# SCH_sfstgr_2023-11-16.net
KiCad netlist of a schematic drawn in EasyEDA
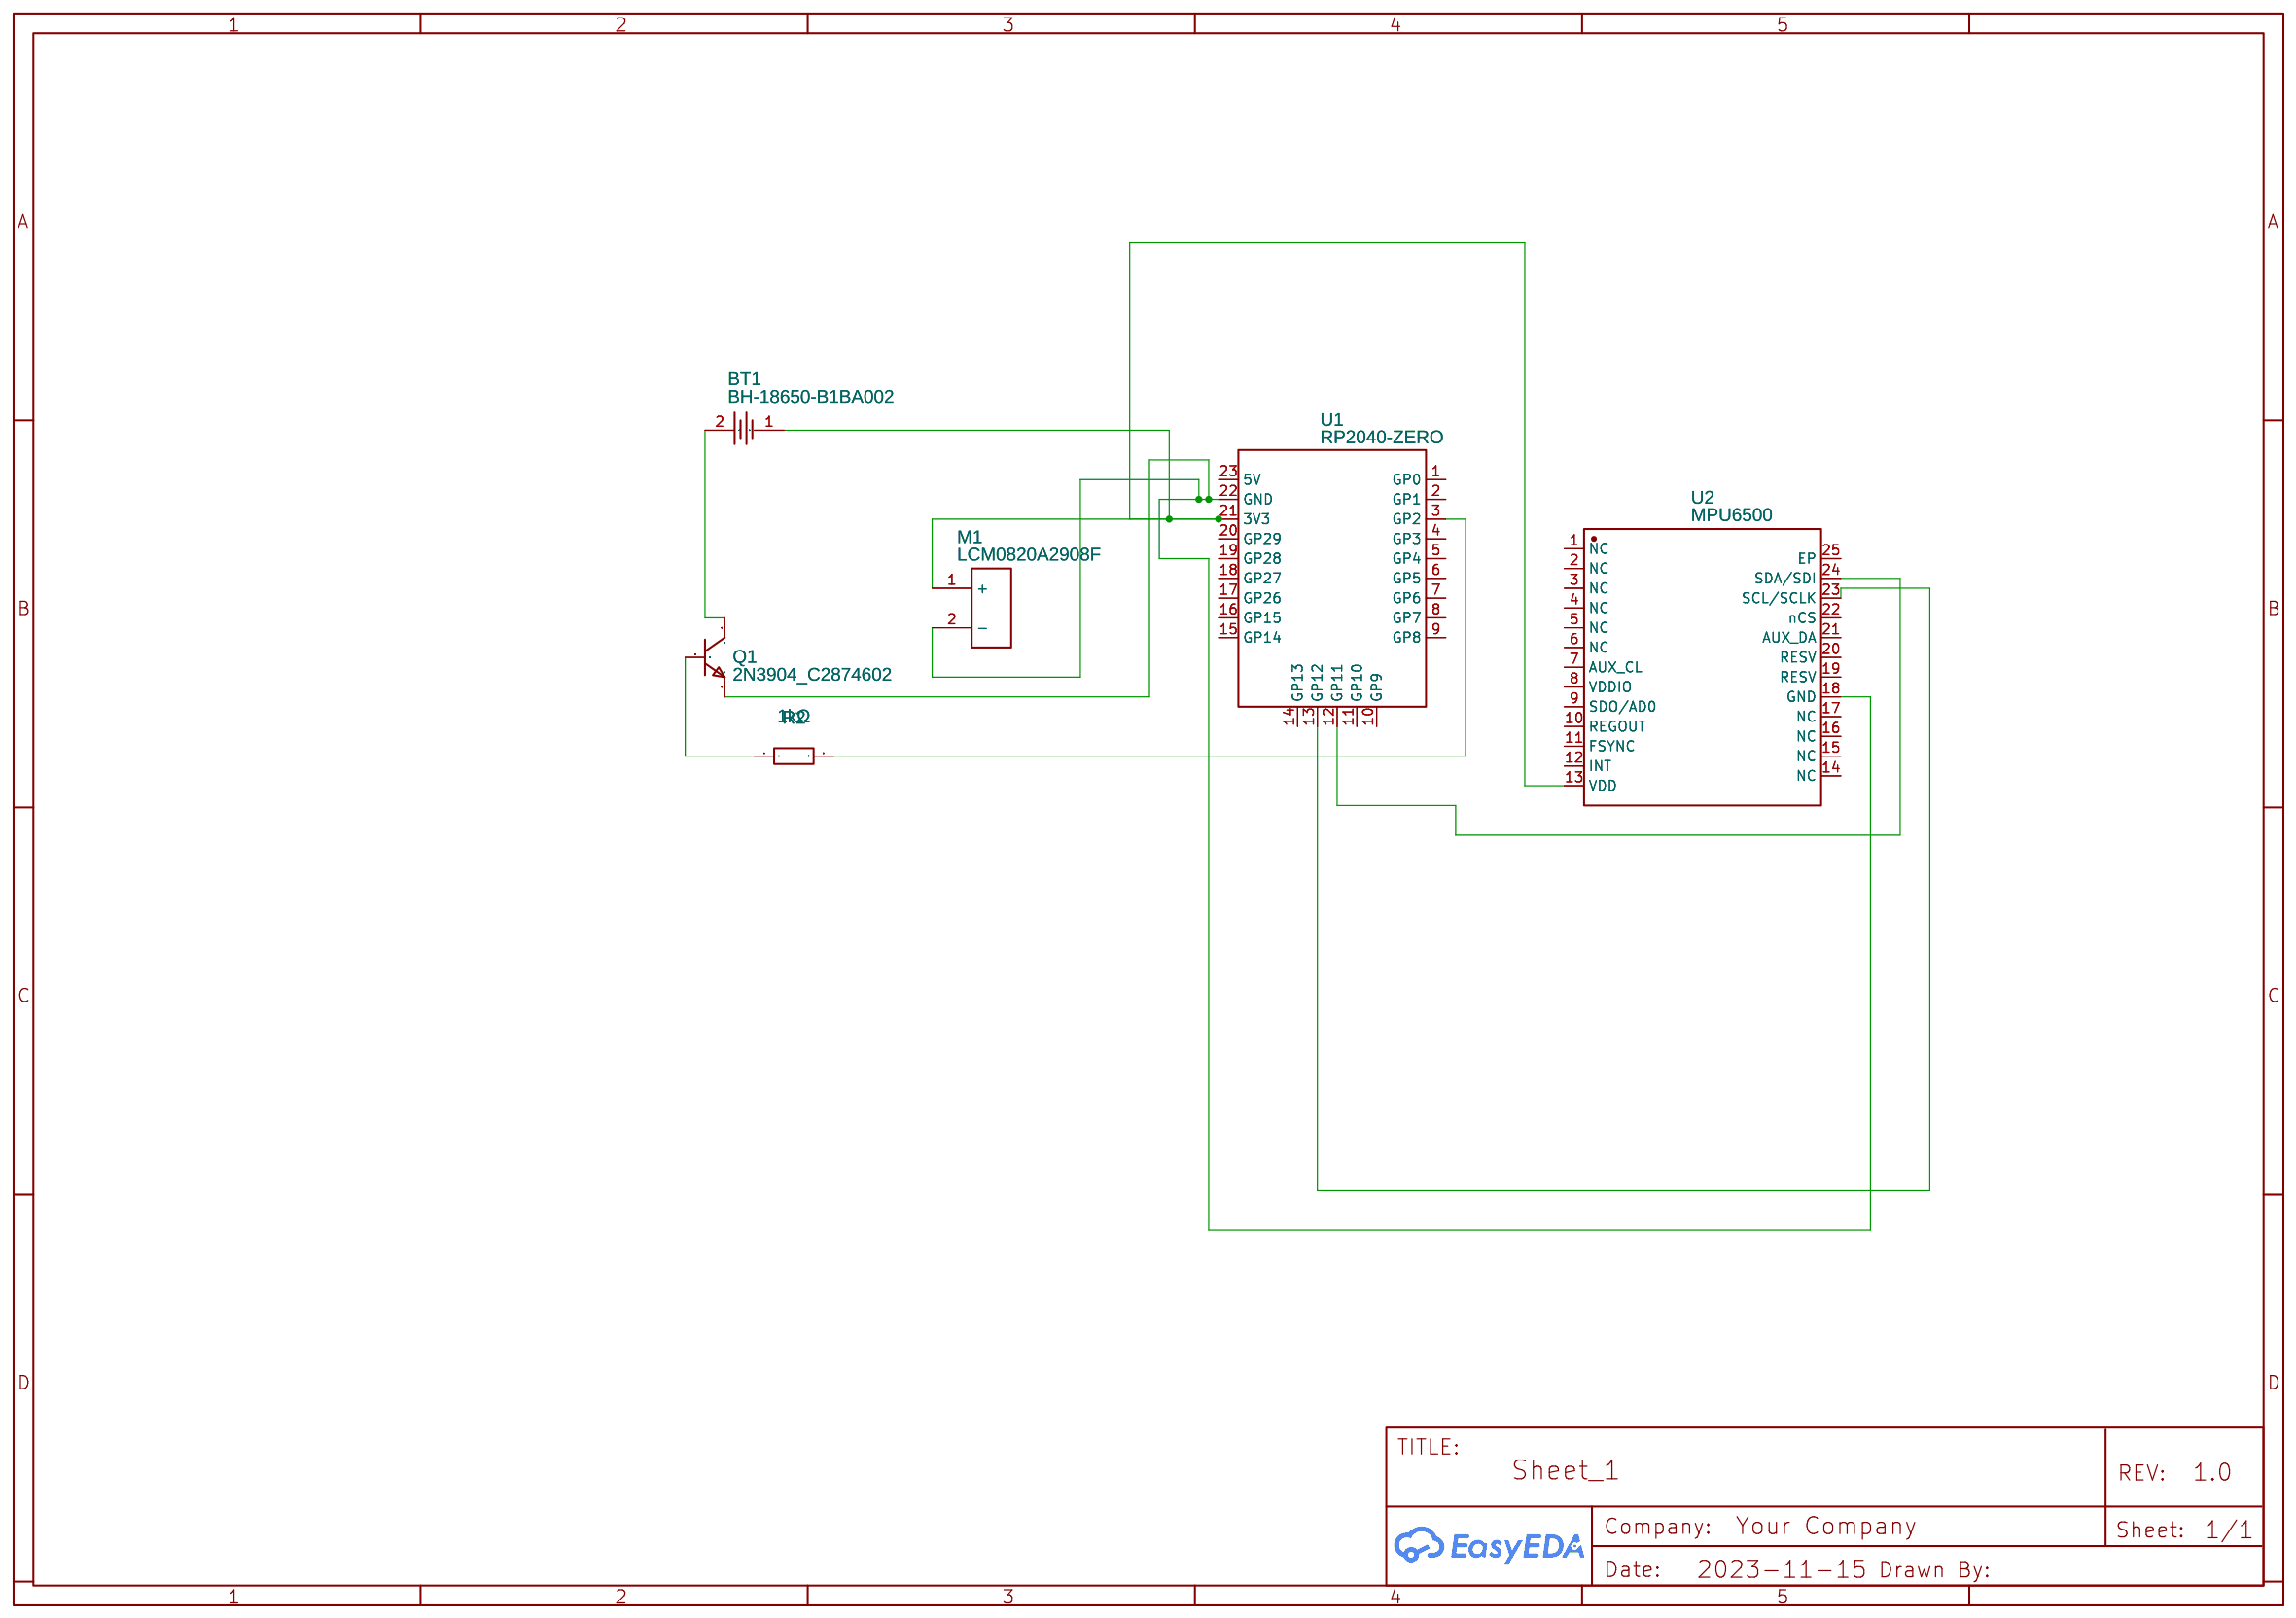
[diagram p0: schematic sheet]

(export (version "E")
  (design (tool "Eeschema 10.0.6"))
  (components
    (comp (ref "BT1")
      (value "BH-18650-B1BA002")
      (fields (field (name "Manufacturer") "MYOUNG(美阳)"))
      (libsource (lib "") (part "BH-18650-B1BA002"))
    )
    (comp (ref "M1") (value "LCM0820A2908F") (libsource (lib "") (part "LCM0820A2908F")))
    (comp (ref "Q1")
      (value "2N3904_C2874602")
      (fields (field (name "Manufacturer Part") "2N3904") (field (name "Manufacturer") "JSMSEMI(杰盛微)"))
      (libsource (lib "") (part "2N3904_C2874602"))
    )
    (comp (ref "R2")
      (value "1kΩ")
      (fields
        (field (name "Manufacturer Part") "QR0402F1K00Q10Z")
        (field (name "Manufacturer") "EVER OHMS(天二科技)")
      )
      (libsource (lib "") (part "QR0402F1KQ10"))
    )
    (comp (ref "U1")
      (value "RP2040-ZERO")
      (fields
        (field (name "Manufacturer Part") "RP2040-Zero")
        (field (name "Manufacturer") "Waveshare(微雪电子)")
      )
      (libsource (lib "") (part "RP2040-ZERO"))
    )
    (comp (ref "U2")
      (value "MPU6500")
      (fields (field (name "Manufacturer") "TDK InvenSense(应美盛)"))
      (libsource (lib "") (part "MPU6500"))
    )
  )
  (nets
    (net (code "1") (name "Net-(M1-+)") (class "Default")
      (node (ref "BT1") (pin "1") (pinfunction "1_1") (pintype "input"))
      (node (ref "M1") (pin "1") (pinfunction "+_1") (pintype "unspecified"))
      (node (ref "U1") (pin "21") (pinfunction "3V3_21") (pintype "unspecified"))
      (node (ref "U2") (pin "13") (pinfunction "VDD_13") (pintype "unspecified"))
    )
    (net (code "2") (name "Net-(M1--)") (class "Default")
      (node (ref "M1") (pin "2") (pinfunction "-_2") (pintype "unspecified"))
      (node (ref "Q1") (pin "1") (pinfunction "E_1") (pintype "unspecified"))
      (node (ref "U1") (pin "22") (pinfunction "GND_22") (pintype "unspecified"))
      (node (ref "U2") (pin "18") (pinfunction "GND_18") (pintype "unspecified"))
    )
    (net (code "3") (name "Net-(Q1-B)") (class "Default")
      (node (ref "Q1") (pin "2") (pinfunction "B_2") (pintype "unspecified"))
      (node (ref "R2") (pin "1") (pinfunction "1_1") (pintype "unspecified"))
    )
    (net (code "4") (name "Net-(Q1-C)") (class "Default")
      (node (ref "BT1") (pin "2") (pinfunction "2_2") (pintype "input"))
      (node (ref "Q1") (pin "3") (pinfunction "C_3") (pintype "unspecified"))
    )
    (net (code "5") (name "Net-(U1-GP2)") (class "Default")
      (node (ref "R2") (pin "2") (pinfunction "2_2") (pintype "unspecified"))
      (node (ref "U1") (pin "3") (pinfunction "GP2_3") (pintype "unspecified"))
    )
    (net (code "6") (name "Net-(U1-GP11)") (class "Default")
      (node (ref "U1") (pin "12") (pinfunction "GP11_12") (pintype "unspecified"))
      (node (ref "U2") (pin "24") (pinfunction "SDA/SDI_24") (pintype "unspecified"))
    )
    (net (code "7") (name "Net-(U1-GP12)") (class "Default")
      (node (ref "U1") (pin "13") (pinfunction "GP12_13") (pintype "unspecified"))
      (node (ref "U2") (pin "23") (pinfunction "SCL/SCLK_23") (pintype "unspecified"))
    )
    (net (code "8") (name "unconnected-(U1-5V-Pad23)") (class "Default")
      (node (ref "U1") (pin "23") (pinfunction "5V_23") (pintype "unspecified"))
    )
    (net (code "9") (name "unconnected-(U1-GP0-Pad1)") (class "Default")
      (node (ref "U1") (pin "1") (pinfunction "GP0_1") (pintype "unspecified"))
    )
    (net (code "10") (name "unconnected-(U1-GP1-Pad2)") (class "Default")
      (node (ref "U1") (pin "2") (pinfunction "GP1_2") (pintype "unspecified"))
    )
    (net (code "11") (name "unconnected-(U1-GP3-Pad4)") (class "Default")
      (node (ref "U1") (pin "4") (pinfunction "GP3_4") (pintype "unspecified"))
    )
    (net (code "12") (name "unconnected-(U1-GP4-Pad5)") (class "Default")
      (node (ref "U1") (pin "5") (pinfunction "GP4_5") (pintype "unspecified"))
    )
    (net (code "13") (name "unconnected-(U1-GP5-Pad6)") (class "Default")
      (node (ref "U1") (pin "6") (pinfunction "GP5_6") (pintype "unspecified"))
    )
    (net (code "14") (name "unconnected-(U1-GP6-Pad7)") (class "Default")
      (node (ref "U1") (pin "7") (pinfunction "GP6_7") (pintype "unspecified"))
    )
    (net (code "15") (name "unconnected-(U1-GP7-Pad8)") (class "Default")
      (node (ref "U1") (pin "8") (pinfunction "GP7_8") (pintype "unspecified"))
    )
    (net (code "16") (name "unconnected-(U1-GP8-Pad9)") (class "Default")
      (node (ref "U1") (pin "9") (pinfunction "GP8_9") (pintype "unspecified"))
    )
    (net (code "17") (name "unconnected-(U1-GP9-Pad10)") (class "Default")
      (node (ref "U1") (pin "10") (pinfunction "GP9_10") (pintype "unspecified"))
    )
    (net (code "18") (name "unconnected-(U1-GP10-Pad11)") (class "Default")
      (node (ref "U1") (pin "11") (pinfunction "GP10_11") (pintype "unspecified"))
    )
    (net (code "19") (name "unconnected-(U1-GP13-Pad14)") (class "Default")
      (node (ref "U1") (pin "14") (pinfunction "GP13_14") (pintype "unspecified"))
    )
    (net (code "20") (name "unconnected-(U1-GP14-Pad15)") (class "Default")
      (node (ref "U1") (pin "15") (pinfunction "GP14_15") (pintype "unspecified"))
    )
    (net (code "21") (name "unconnected-(U1-GP15-Pad16)") (class "Default")
      (node (ref "U1") (pin "16") (pinfunction "GP15_16") (pintype "unspecified"))
    )
    (net (code "22") (name "unconnected-(U1-GP26-Pad17)") (class "Default")
      (node (ref "U1") (pin "17") (pinfunction "GP26_17") (pintype "unspecified"))
    )
    (net (code "23") (name "unconnected-(U1-GP27-Pad18)") (class "Default")
      (node (ref "U1") (pin "18") (pinfunction "GP27_18") (pintype "unspecified"))
    )
    (net (code "24") (name "unconnected-(U1-GP28-Pad19)") (class "Default")
      (node (ref "U1") (pin "19") (pinfunction "GP28_19") (pintype "unspecified"))
    )
    (net (code "25") (name "unconnected-(U1-GP29-Pad20)") (class "Default")
      (node (ref "U1") (pin "20") (pinfunction "GP29_20") (pintype "unspecified"))
    )
    (net (code "26") (name "unconnected-(U2-AUX_CL-Pad7)") (class "Default")
      (node (ref "U2") (pin "7") (pinfunction "AUX_CL_7") (pintype "unspecified"))
    )
    (net (code "27") (name "unconnected-(U2-AUX_DA-Pad21)") (class "Default")
      (node (ref "U2") (pin "21") (pinfunction "AUX_DA_21") (pintype "unspecified"))
    )
    (net (code "28") (name "unconnected-(U2-EP-Pad25)") (class "Default")
      (node (ref "U2") (pin "25") (pinfunction "EP_25") (pintype "unspecified"))
    )
    (net (code "29") (name "unconnected-(U2-FSYNC-Pad11)") (class "Default")
      (node (ref "U2") (pin "11") (pinfunction "FSYNC_11") (pintype "unspecified"))
    )
    (net (code "30") (name "unconnected-(U2-INT-Pad12)") (class "Default")
      (node (ref "U2") (pin "12") (pinfunction "INT_12") (pintype "unspecified"))
    )
    (net (code "31") (name "unconnected-(U2-NC-Pad1)") (class "Default")
      (node (ref "U2") (pin "1") (pinfunction "NC_1") (pintype "unspecified"))
    )
    (net (code "32") (name "unconnected-(U2-NC-Pad2)") (class "Default")
      (node (ref "U2") (pin "2") (pinfunction "NC_2") (pintype "unspecified"))
    )
    (net (code "33") (name "unconnected-(U2-NC-Pad3)") (class "Default")
      (node (ref "U2") (pin "3") (pinfunction "NC_3") (pintype "unspecified"))
    )
    (net (code "34") (name "unconnected-(U2-NC-Pad4)") (class "Default")
      (node (ref "U2") (pin "4") (pinfunction "NC_4") (pintype "unspecified"))
    )
    (net (code "35") (name "unconnected-(U2-NC-Pad5)") (class "Default")
      (node (ref "U2") (pin "5") (pinfunction "NC_5") (pintype "unspecified"))
    )
    (net (code "36") (name "unconnected-(U2-NC-Pad6)") (class "Default")
      (node (ref "U2") (pin "6") (pinfunction "NC_6") (pintype "unspecified"))
    )
    (net (code "37") (name "unconnected-(U2-NC-Pad14)") (class "Default")
      (node (ref "U2") (pin "14") (pinfunction "NC_14") (pintype "unspecified"))
    )
    (net (code "38") (name "unconnected-(U2-NC-Pad15)") (class "Default")
      (node (ref "U2") (pin "15") (pinfunction "NC_15") (pintype "unspecified"))
    )
    (net (code "39") (name "unconnected-(U2-NC-Pad16)") (class "Default")
      (node (ref "U2") (pin "16") (pinfunction "NC_16") (pintype "unspecified"))
    )
    (net (code "40") (name "unconnected-(U2-NC-Pad17)") (class "Default")
      (node (ref "U2") (pin "17") (pinfunction "NC_17") (pintype "unspecified"))
    )
    (net (code "41") (name "unconnected-(U2-REGOUT-Pad10)") (class "Default")
      (node (ref "U2") (pin "10") (pinfunction "REGOUT_10") (pintype "unspecified"))
    )
    (net (code "42") (name "unconnected-(U2-RESV-Pad19)") (class "Default")
      (node (ref "U2") (pin "19") (pinfunction "RESV_19") (pintype "unspecified"))
    )
    (net (code "43") (name "unconnected-(U2-RESV-Pad20)") (class "Default")
      (node (ref "U2") (pin "20") (pinfunction "RESV_20") (pintype "unspecified"))
    )
    (net (code "44") (name "unconnected-(U2-SDO{slash}AD0-Pad9)") (class "Default")
      (node (ref "U2") (pin "9") (pinfunction "SDO/AD0_9") (pintype "unspecified"))
    )
    (net (code "45") (name "unconnected-(U2-VDDIO-Pad8)") (class "Default")
      (node (ref "U2") (pin "8") (pinfunction "VDDIO_8") (pintype "unspecified"))
    )
    (net (code "46") (name "unconnected-(U2-nCS-Pad22)") (class "Default")
      (node (ref "U2") (pin "22") (pinfunction "nCS_22") (pintype "unspecified"))
    )
  )
)
